# DSKY_KEY.net
KiCad netlist of a schematic drawn in EAGLE
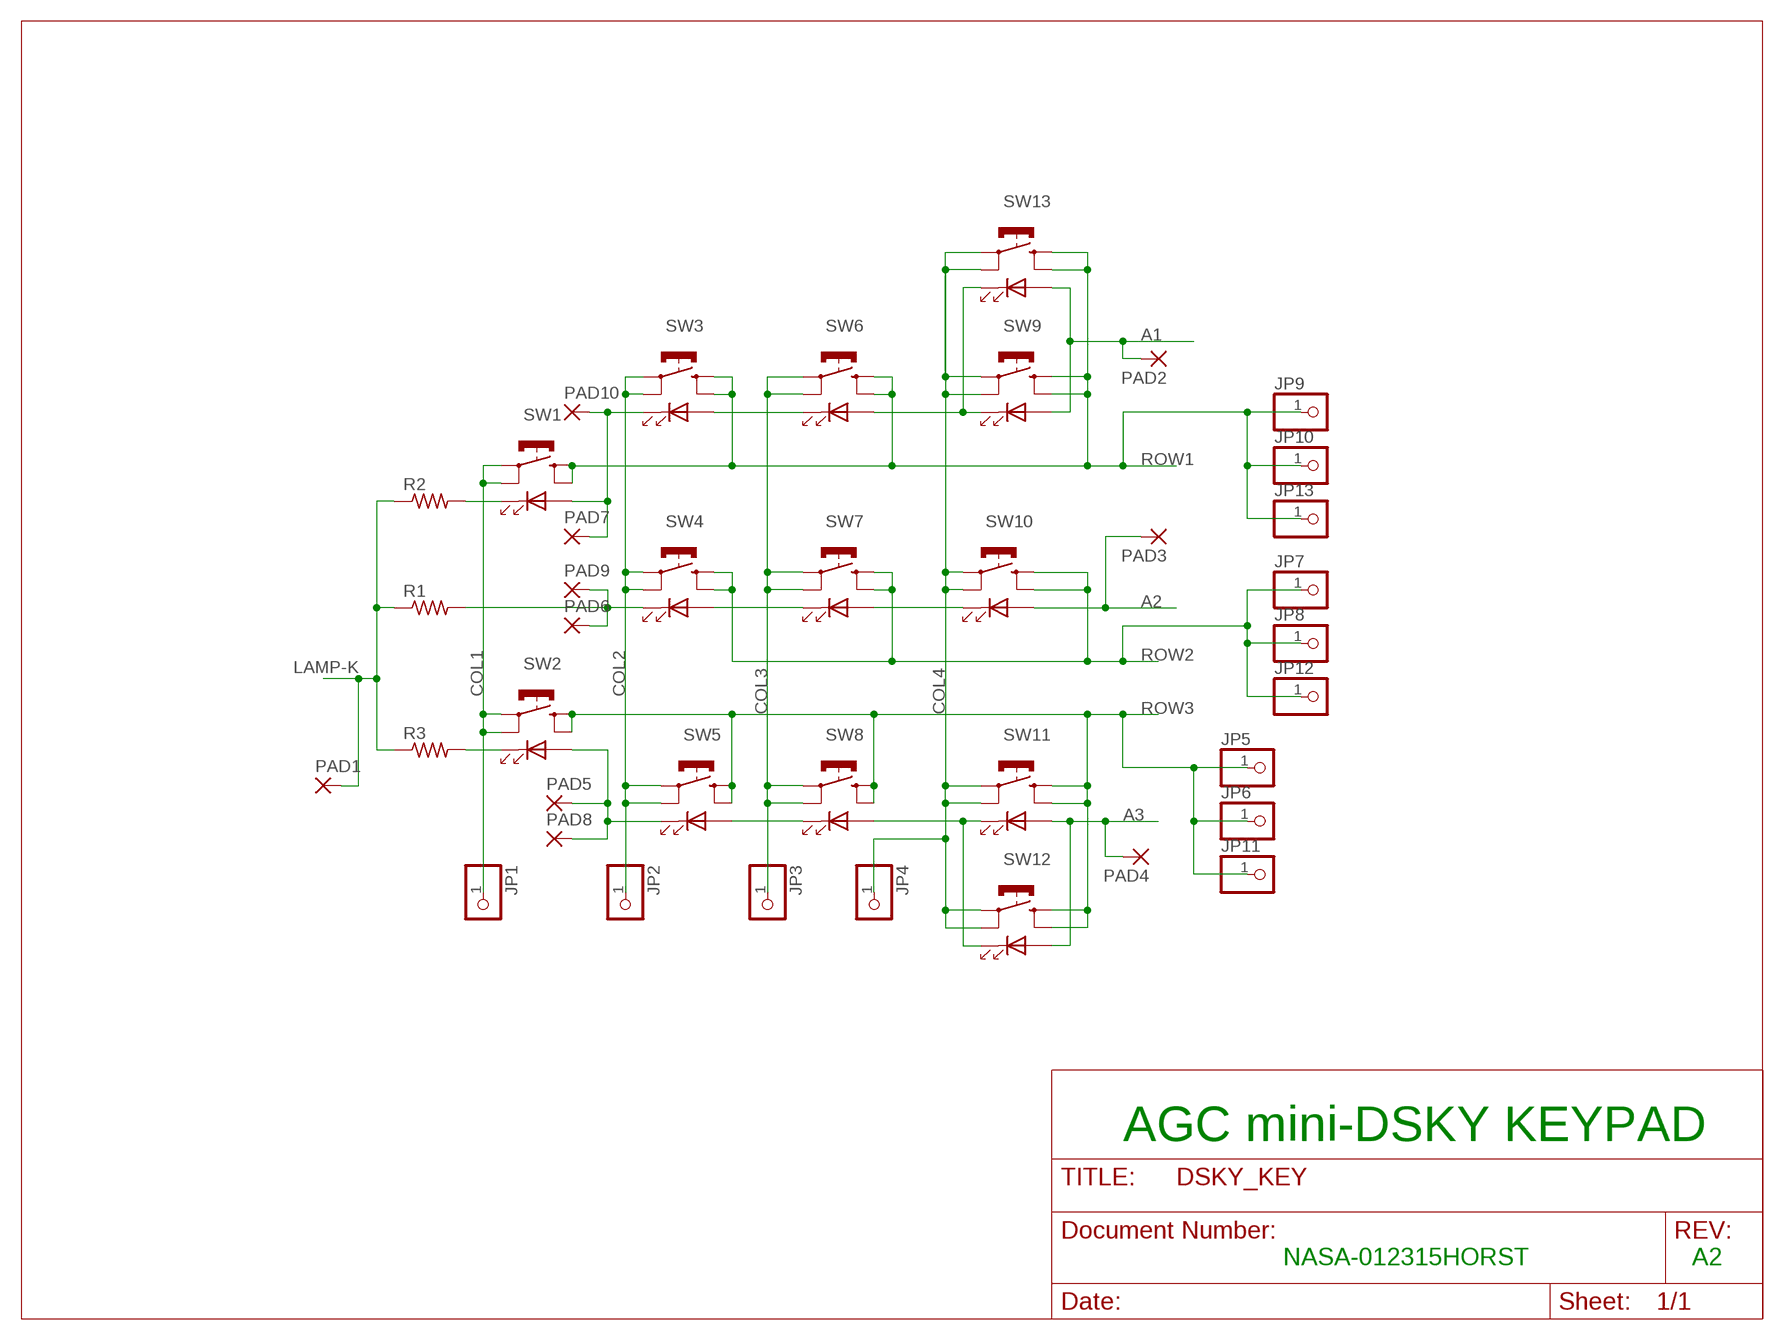
[diagram p0: schematic, sheet 1]

(export (version "E")
  (design (tool "Eeschema 10.0.6"))
  (components
    (comp (ref "JP1")
      (value "PINHD-1X1")
      (footprint "eagle-import:1X01")
      (libsource (lib "eagle-import") (part "PINHD-1X1"))
    )
    (comp (ref "JP2")
      (value "PINHD-1X1")
      (footprint "eagle-import:1X01")
      (libsource (lib "eagle-import") (part "PINHD-1X1"))
    )
    (comp (ref "JP3")
      (value "PINHD-1X1")
      (footprint "eagle-import:1X01")
      (libsource (lib "eagle-import") (part "PINHD-1X1"))
    )
    (comp (ref "JP4")
      (value "PINHD-1X1")
      (footprint "eagle-import:1X01")
      (libsource (lib "eagle-import") (part "PINHD-1X1"))
    )
    (comp (ref "JP5")
      (value "PINHD-1X1")
      (footprint "eagle-import:1X01")
      (libsource (lib "eagle-import") (part "PINHD-1X1"))
    )
    (comp (ref "JP6")
      (value "PINHD-1X1")
      (footprint "eagle-import:1X01")
      (libsource (lib "eagle-import") (part "PINHD-1X1"))
    )
    (comp (ref "JP7")
      (value "PINHD-1X1")
      (footprint "eagle-import:1X01")
      (libsource (lib "eagle-import") (part "PINHD-1X1"))
    )
    (comp (ref "JP8")
      (value "PINHD-1X1")
      (footprint "eagle-import:1X01")
      (libsource (lib "eagle-import") (part "PINHD-1X1"))
    )
    (comp (ref "JP9")
      (value "PINHD-1X1")
      (footprint "eagle-import:1X01")
      (libsource (lib "eagle-import") (part "PINHD-1X1"))
    )
    (comp (ref "JP10")
      (value "PINHD-1X1")
      (footprint "eagle-import:1X01")
      (libsource (lib "eagle-import") (part "PINHD-1X1"))
    )
    (comp (ref "JP11")
      (value "PINHD-1X1")
      (footprint "eagle-import:1X01")
      (libsource (lib "eagle-import") (part "PINHD-1X1"))
    )
    (comp (ref "JP12")
      (value "PINHD-1X1")
      (footprint "eagle-import:1X01")
      (libsource (lib "eagle-import") (part "PINHD-1X1"))
    )
    (comp (ref "JP13")
      (value "PINHD-1X1")
      (footprint "eagle-import:1X01")
      (libsource (lib "eagle-import") (part "PINHD-1X1"))
    )
    (comp (ref "PAD1")
      (value "2,54/0,8")
      (footprint "eagle-import:2,54_0,8")
      (libsource (lib "eagle-import") (part "2,54/0,8"))
    )
    (comp (ref "PAD2")
      (value "1,6/0,8")
      (footprint "eagle-import:1,6_0,8")
      (libsource (lib "eagle-import") (part "1,6/0,8"))
    )
    (comp (ref "PAD3")
      (value "1,6/0,8")
      (footprint "eagle-import:1,6_0,8")
      (libsource (lib "eagle-import") (part "1,6/0,8"))
    )
    (comp (ref "PAD4")
      (value "1,6/0,8")
      (footprint "eagle-import:1,6_0,8")
      (libsource (lib "eagle-import") (part "1,6/0,8"))
    )
    (comp (ref "PAD5")
      (value "1,6/0,8")
      (footprint "eagle-import:1,6_0,8")
      (libsource (lib "eagle-import") (part "1,6/0,8"))
    )
    (comp (ref "PAD6")
      (value "1,6/0,8")
      (footprint "eagle-import:1,6_0,8")
      (libsource (lib "eagle-import") (part "1,6/0,8"))
    )
    (comp (ref "PAD7")
      (value "1,6/0,8")
      (footprint "eagle-import:1,6_0,8")
      (libsource (lib "eagle-import") (part "1,6/0,8"))
    )
    (comp (ref "PAD8")
      (value "1,6/0,8")
      (footprint "eagle-import:1,6_0,8")
      (libsource (lib "eagle-import") (part "1,6/0,8"))
    )
    (comp (ref "PAD9")
      (value "1,6/0,8")
      (footprint "eagle-import:1,6_0,8")
      (libsource (lib "eagle-import") (part "1,6/0,8"))
    )
    (comp (ref "PAD10")
      (value "1,6/0,8")
      (footprint "eagle-import:1,6_0,8")
      (libsource (lib "eagle-import") (part "1,6/0,8"))
    )
    (comp (ref "R1")
      (value "R-US_0204/7")
      (footprint "eagle-import:0204_7")
      (libsource (lib "eagle-import") (part "R-US_0204/7"))
    )
    (comp (ref "R2")
      (value "R-US_0204/7")
      (footprint "eagle-import:0204_7")
      (libsource (lib "eagle-import") (part "R-US_0204/7"))
    )
    (comp (ref "R3")
      (value "R-US_0204/7")
      (footprint "eagle-import:0204_7")
      (libsource (lib "eagle-import") (part "R-US_0204/7"))
    )
    (comp (ref "SW1")
      (value "B3E-1100")
      (footprint "eagle-import:B3E-11XX")
      (libsource (lib "eagle-import") (part "B3E-1100"))
    )
    (comp (ref "SW2")
      (value "B3E-1100")
      (footprint "eagle-import:B3E-11XX")
      (libsource (lib "eagle-import") (part "B3E-1100"))
    )
    (comp (ref "SW3")
      (value "B3E-1100")
      (footprint "eagle-import:B3E-11XX")
      (libsource (lib "eagle-import") (part "B3E-1100"))
    )
    (comp (ref "SW4")
      (value "B3E-1100")
      (footprint "eagle-import:B3E-11XX")
      (libsource (lib "eagle-import") (part "B3E-1100"))
    )
    (comp (ref "SW5")
      (value "B3E-1100")
      (footprint "eagle-import:B3E-11XX")
      (libsource (lib "eagle-import") (part "B3E-1100"))
    )
    (comp (ref "SW6")
      (value "B3E-1100")
      (footprint "eagle-import:B3E-11XX")
      (libsource (lib "eagle-import") (part "B3E-1100"))
    )
    (comp (ref "SW7")
      (value "B3E-1100")
      (footprint "eagle-import:B3E-11XX")
      (libsource (lib "eagle-import") (part "B3E-1100"))
    )
    (comp (ref "SW8")
      (value "B3E-1100")
      (footprint "eagle-import:B3E-11XX")
      (libsource (lib "eagle-import") (part "B3E-1100"))
    )
    (comp (ref "SW9")
      (value "B3E-1100")
      (footprint "eagle-import:B3E-11XX")
      (libsource (lib "eagle-import") (part "B3E-1100"))
    )
    (comp (ref "SW10")
      (value "B3E-1100")
      (footprint "eagle-import:B3E-11XX")
      (libsource (lib "eagle-import") (part "B3E-1100"))
    )
    (comp (ref "SW11")
      (value "B3E-1100")
      (footprint "eagle-import:B3E-11XX")
      (libsource (lib "eagle-import") (part "B3E-1100"))
    )
    (comp (ref "SW12")
      (value "B3E-1100")
      (footprint "eagle-import:B3E-11XX")
      (libsource (lib "eagle-import") (part "B3E-1100"))
    )
    (comp (ref "SW13")
      (value "B3E-1100")
      (footprint "eagle-import:B3E-11XX")
      (libsource (lib "eagle-import") (part "B3E-1100"))
    )
  )
  (nets
    (net (code "1") (name "/A1") (class "Default")
      (node (ref "PAD2") (pin "1") (pinfunction "P_1") (pintype "passive"))
      (node (ref "SW13") (pin "P$5") (pinfunction "A_P$5") (pintype "passive"))
      (node (ref "SW9") (pin "P$5") (pinfunction "A_P$5") (pintype "passive"))
    )
    (net (code "2") (name "/A2") (class "Default")
      (node (ref "PAD3") (pin "1") (pinfunction "P_1") (pintype "passive"))
      (node (ref "SW10") (pin "P$5") (pinfunction "A_P$5") (pintype "passive"))
    )
    (net (code "3") (name "/A3") (class "Default")
      (node (ref "PAD4") (pin "1") (pinfunction "P_1") (pintype "passive"))
      (node (ref "SW11") (pin "P$5") (pinfunction "A_P$5") (pintype "passive"))
      (node (ref "SW12") (pin "P$5") (pinfunction "A_P$5") (pintype "passive"))
    )
    (net (code "4") (name "/COL1") (class "Default")
      (node (ref "JP1") (pin "1") (pinfunction "1_1") (pintype "passive"))
      (node (ref "SW1") (pin "P$1") (pinfunction "P_P$1") (pintype "passive"))
      (node (ref "SW1") (pin "P$2") (pinfunction "P1_P$2") (pintype "passive"))
      (node (ref "SW2") (pin "P$1") (pinfunction "P_P$1") (pintype "passive"))
      (node (ref "SW2") (pin "P$2") (pinfunction "P1_P$2") (pintype "passive"))
    )
    (net (code "5") (name "/COL2") (class "Default")
      (node (ref "JP2") (pin "1") (pinfunction "1_1") (pintype "passive"))
      (node (ref "SW3") (pin "P$1") (pinfunction "P_P$1") (pintype "passive"))
      (node (ref "SW3") (pin "P$2") (pinfunction "P1_P$2") (pintype "passive"))
      (node (ref "SW4") (pin "P$1") (pinfunction "P_P$1") (pintype "passive"))
      (node (ref "SW4") (pin "P$2") (pinfunction "P1_P$2") (pintype "passive"))
      (node (ref "SW5") (pin "P$1") (pinfunction "P_P$1") (pintype "passive"))
      (node (ref "SW5") (pin "P$2") (pinfunction "P1_P$2") (pintype "passive"))
    )
    (net (code "6") (name "/COL3") (class "Default")
      (node (ref "JP3") (pin "1") (pinfunction "1_1") (pintype "passive"))
      (node (ref "SW6") (pin "P$1") (pinfunction "P_P$1") (pintype "passive"))
      (node (ref "SW6") (pin "P$2") (pinfunction "P1_P$2") (pintype "passive"))
      (node (ref "SW7") (pin "P$1") (pinfunction "P_P$1") (pintype "passive"))
      (node (ref "SW7") (pin "P$2") (pinfunction "P1_P$2") (pintype "passive"))
      (node (ref "SW8") (pin "P$1") (pinfunction "P_P$1") (pintype "passive"))
      (node (ref "SW8") (pin "P$2") (pinfunction "P1_P$2") (pintype "passive"))
    )
    (net (code "7") (name "/COL4") (class "Default")
      (node (ref "JP4") (pin "1") (pinfunction "1_1") (pintype "passive"))
      (node (ref "SW10") (pin "P$1") (pinfunction "P_P$1") (pintype "passive"))
      (node (ref "SW10") (pin "P$2") (pinfunction "P1_P$2") (pintype "passive"))
      (node (ref "SW11") (pin "P$1") (pinfunction "P_P$1") (pintype "passive"))
      (node (ref "SW11") (pin "P$2") (pinfunction "P1_P$2") (pintype "passive"))
      (node (ref "SW12") (pin "P$1") (pinfunction "P_P$1") (pintype "passive"))
      (node (ref "SW12") (pin "P$2") (pinfunction "P1_P$2") (pintype "passive"))
      (node (ref "SW13") (pin "P$1") (pinfunction "P_P$1") (pintype "passive"))
      (node (ref "SW13") (pin "P$2") (pinfunction "P1_P$2") (pintype "passive"))
      (node (ref "SW9") (pin "P$1") (pinfunction "P_P$1") (pintype "passive"))
      (node (ref "SW9") (pin "P$2") (pinfunction "P1_P$2") (pintype "passive"))
    )
    (net (code "8") (name "/LAMP-K") (class "Default")
      (node (ref "PAD1") (pin "1") (pinfunction "P_1") (pintype "passive"))
      (node (ref "R1") (pin "1") (pinfunction "1_1") (pintype "passive"))
      (node (ref "R2") (pin "1") (pinfunction "1_1") (pintype "passive"))
      (node (ref "R3") (pin "1") (pinfunction "1_1") (pintype "passive"))
    )
    (net (code "9") (name "/ROW1") (class "Default")
      (node (ref "JP10") (pin "1") (pinfunction "1_1") (pintype "passive"))
      (node (ref "JP13") (pin "1") (pinfunction "1_1") (pintype "passive"))
      (node (ref "JP9") (pin "1") (pinfunction "1_1") (pintype "passive"))
      (node (ref "SW1") (pin "P$3") (pinfunction "S_P$3") (pintype "passive"))
      (node (ref "SW1") (pin "P$4") (pinfunction "S1_P$4") (pintype "passive"))
      (node (ref "SW13") (pin "P$3") (pinfunction "S_P$3") (pintype "passive"))
      (node (ref "SW13") (pin "P$4") (pinfunction "S1_P$4") (pintype "passive"))
      (node (ref "SW3") (pin "P$3") (pinfunction "S_P$3") (pintype "passive"))
      (node (ref "SW3") (pin "P$4") (pinfunction "S1_P$4") (pintype "passive"))
      (node (ref "SW6") (pin "P$3") (pinfunction "S_P$3") (pintype "passive"))
      (node (ref "SW6") (pin "P$4") (pinfunction "S1_P$4") (pintype "passive"))
      (node (ref "SW9") (pin "P$3") (pinfunction "S_P$3") (pintype "passive"))
      (node (ref "SW9") (pin "P$4") (pinfunction "S1_P$4") (pintype "passive"))
    )
    (net (code "10") (name "/ROW2") (class "Default")
      (node (ref "JP12") (pin "1") (pinfunction "1_1") (pintype "passive"))
      (node (ref "JP7") (pin "1") (pinfunction "1_1") (pintype "passive"))
      (node (ref "JP8") (pin "1") (pinfunction "1_1") (pintype "passive"))
      (node (ref "SW10") (pin "P$3") (pinfunction "S_P$3") (pintype "passive"))
      (node (ref "SW10") (pin "P$4") (pinfunction "S1_P$4") (pintype "passive"))
      (node (ref "SW4") (pin "P$3") (pinfunction "S_P$3") (pintype "passive"))
      (node (ref "SW4") (pin "P$4") (pinfunction "S1_P$4") (pintype "passive"))
      (node (ref "SW7") (pin "P$3") (pinfunction "S_P$3") (pintype "passive"))
      (node (ref "SW7") (pin "P$4") (pinfunction "S1_P$4") (pintype "passive"))
    )
    (net (code "11") (name "/ROW3") (class "Default")
      (node (ref "JP11") (pin "1") (pinfunction "1_1") (pintype "passive"))
      (node (ref "JP5") (pin "1") (pinfunction "1_1") (pintype "passive"))
      (node (ref "JP6") (pin "1") (pinfunction "1_1") (pintype "passive"))
      (node (ref "SW11") (pin "P$3") (pinfunction "S_P$3") (pintype "passive"))
      (node (ref "SW11") (pin "P$4") (pinfunction "S1_P$4") (pintype "passive"))
      (node (ref "SW12") (pin "P$3") (pinfunction "S_P$3") (pintype "passive"))
      (node (ref "SW12") (pin "P$4") (pinfunction "S1_P$4") (pintype "passive"))
      (node (ref "SW2") (pin "P$3") (pinfunction "S_P$3") (pintype "passive"))
      (node (ref "SW2") (pin "P$4") (pinfunction "S1_P$4") (pintype "passive"))
      (node (ref "SW5") (pin "P$3") (pinfunction "S_P$3") (pintype "passive"))
      (node (ref "SW5") (pin "P$4") (pinfunction "S1_P$4") (pintype "passive"))
      (node (ref "SW8") (pin "P$3") (pinfunction "S_P$3") (pintype "passive"))
      (node (ref "SW8") (pin "P$4") (pinfunction "S1_P$4") (pintype "passive"))
    )
    (net (code "12") (name "Net-(PAD5-P)") (class "Default")
      (node (ref "PAD5") (pin "1") (pinfunction "P_1") (pintype "passive"))
      (node (ref "PAD8") (pin "1") (pinfunction "P_1") (pintype "passive"))
      (node (ref "SW2") (pin "P$5") (pinfunction "A_P$5") (pintype "passive"))
      (node (ref "SW5") (pin "P$6") (pinfunction "K_P$6") (pintype "passive"))
    )
    (net (code "13") (name "Net-(PAD6-P)") (class "Default")
      (node (ref "PAD6") (pin "1") (pinfunction "P_1") (pintype "passive"))
      (node (ref "PAD9") (pin "1") (pinfunction "P_1") (pintype "passive"))
      (node (ref "R1") (pin "2") (pinfunction "2_2") (pintype "passive"))
      (node (ref "SW4") (pin "P$6") (pinfunction "K_P$6") (pintype "passive"))
    )
    (net (code "14") (name "Net-(PAD10-P)") (class "Default")
      (node (ref "PAD10") (pin "1") (pinfunction "P_1") (pintype "passive"))
      (node (ref "PAD7") (pin "1") (pinfunction "P_1") (pintype "passive"))
      (node (ref "SW1") (pin "P$5") (pinfunction "A_P$5") (pintype "passive"))
      (node (ref "SW3") (pin "P$6") (pinfunction "K_P$6") (pintype "passive"))
    )
    (net (code "15") (name "Net-(SW1-K)") (class "Default")
      (node (ref "R2") (pin "2") (pinfunction "2_2") (pintype "passive"))
      (node (ref "SW1") (pin "P$6") (pinfunction "K_P$6") (pintype "passive"))
    )
    (net (code "16") (name "Net-(SW2-K)") (class "Default")
      (node (ref "R3") (pin "2") (pinfunction "2_2") (pintype "passive"))
      (node (ref "SW2") (pin "P$6") (pinfunction "K_P$6") (pintype "passive"))
    )
    (net (code "17") (name "Net-(SW3-A)") (class "Default")
      (node (ref "SW3") (pin "P$5") (pinfunction "A_P$5") (pintype "passive"))
      (node (ref "SW6") (pin "P$6") (pinfunction "K_P$6") (pintype "passive"))
    )
    (net (code "18") (name "Net-(SW4-A)") (class "Default")
      (node (ref "SW4") (pin "P$5") (pinfunction "A_P$5") (pintype "passive"))
      (node (ref "SW7") (pin "P$6") (pinfunction "K_P$6") (pintype "passive"))
    )
    (net (code "19") (name "Net-(SW5-A)") (class "Default")
      (node (ref "SW5") (pin "P$5") (pinfunction "A_P$5") (pintype "passive"))
      (node (ref "SW8") (pin "P$6") (pinfunction "K_P$6") (pintype "passive"))
    )
    (net (code "20") (name "Net-(SW10-K)") (class "Default")
      (node (ref "SW10") (pin "P$6") (pinfunction "K_P$6") (pintype "passive"))
      (node (ref "SW7") (pin "P$5") (pinfunction "A_P$5") (pintype "passive"))
    )
    (net (code "21") (name "Net-(SW11-K)") (class "Default")
      (node (ref "SW11") (pin "P$6") (pinfunction "K_P$6") (pintype "passive"))
      (node (ref "SW12") (pin "P$6") (pinfunction "K_P$6") (pintype "passive"))
      (node (ref "SW8") (pin "P$5") (pinfunction "A_P$5") (pintype "passive"))
    )
    (net (code "22") (name "Net-(SW13-K)") (class "Default")
      (node (ref "SW13") (pin "P$6") (pinfunction "K_P$6") (pintype "passive"))
      (node (ref "SW6") (pin "P$5") (pinfunction "A_P$5") (pintype "passive"))
      (node (ref "SW9") (pin "P$6") (pinfunction "K_P$6") (pintype "passive"))
    )
  )
)
